# squawkbox_m_rj11_0_1_0.net
KiCad netlist of a schematic drawn in EAGLE
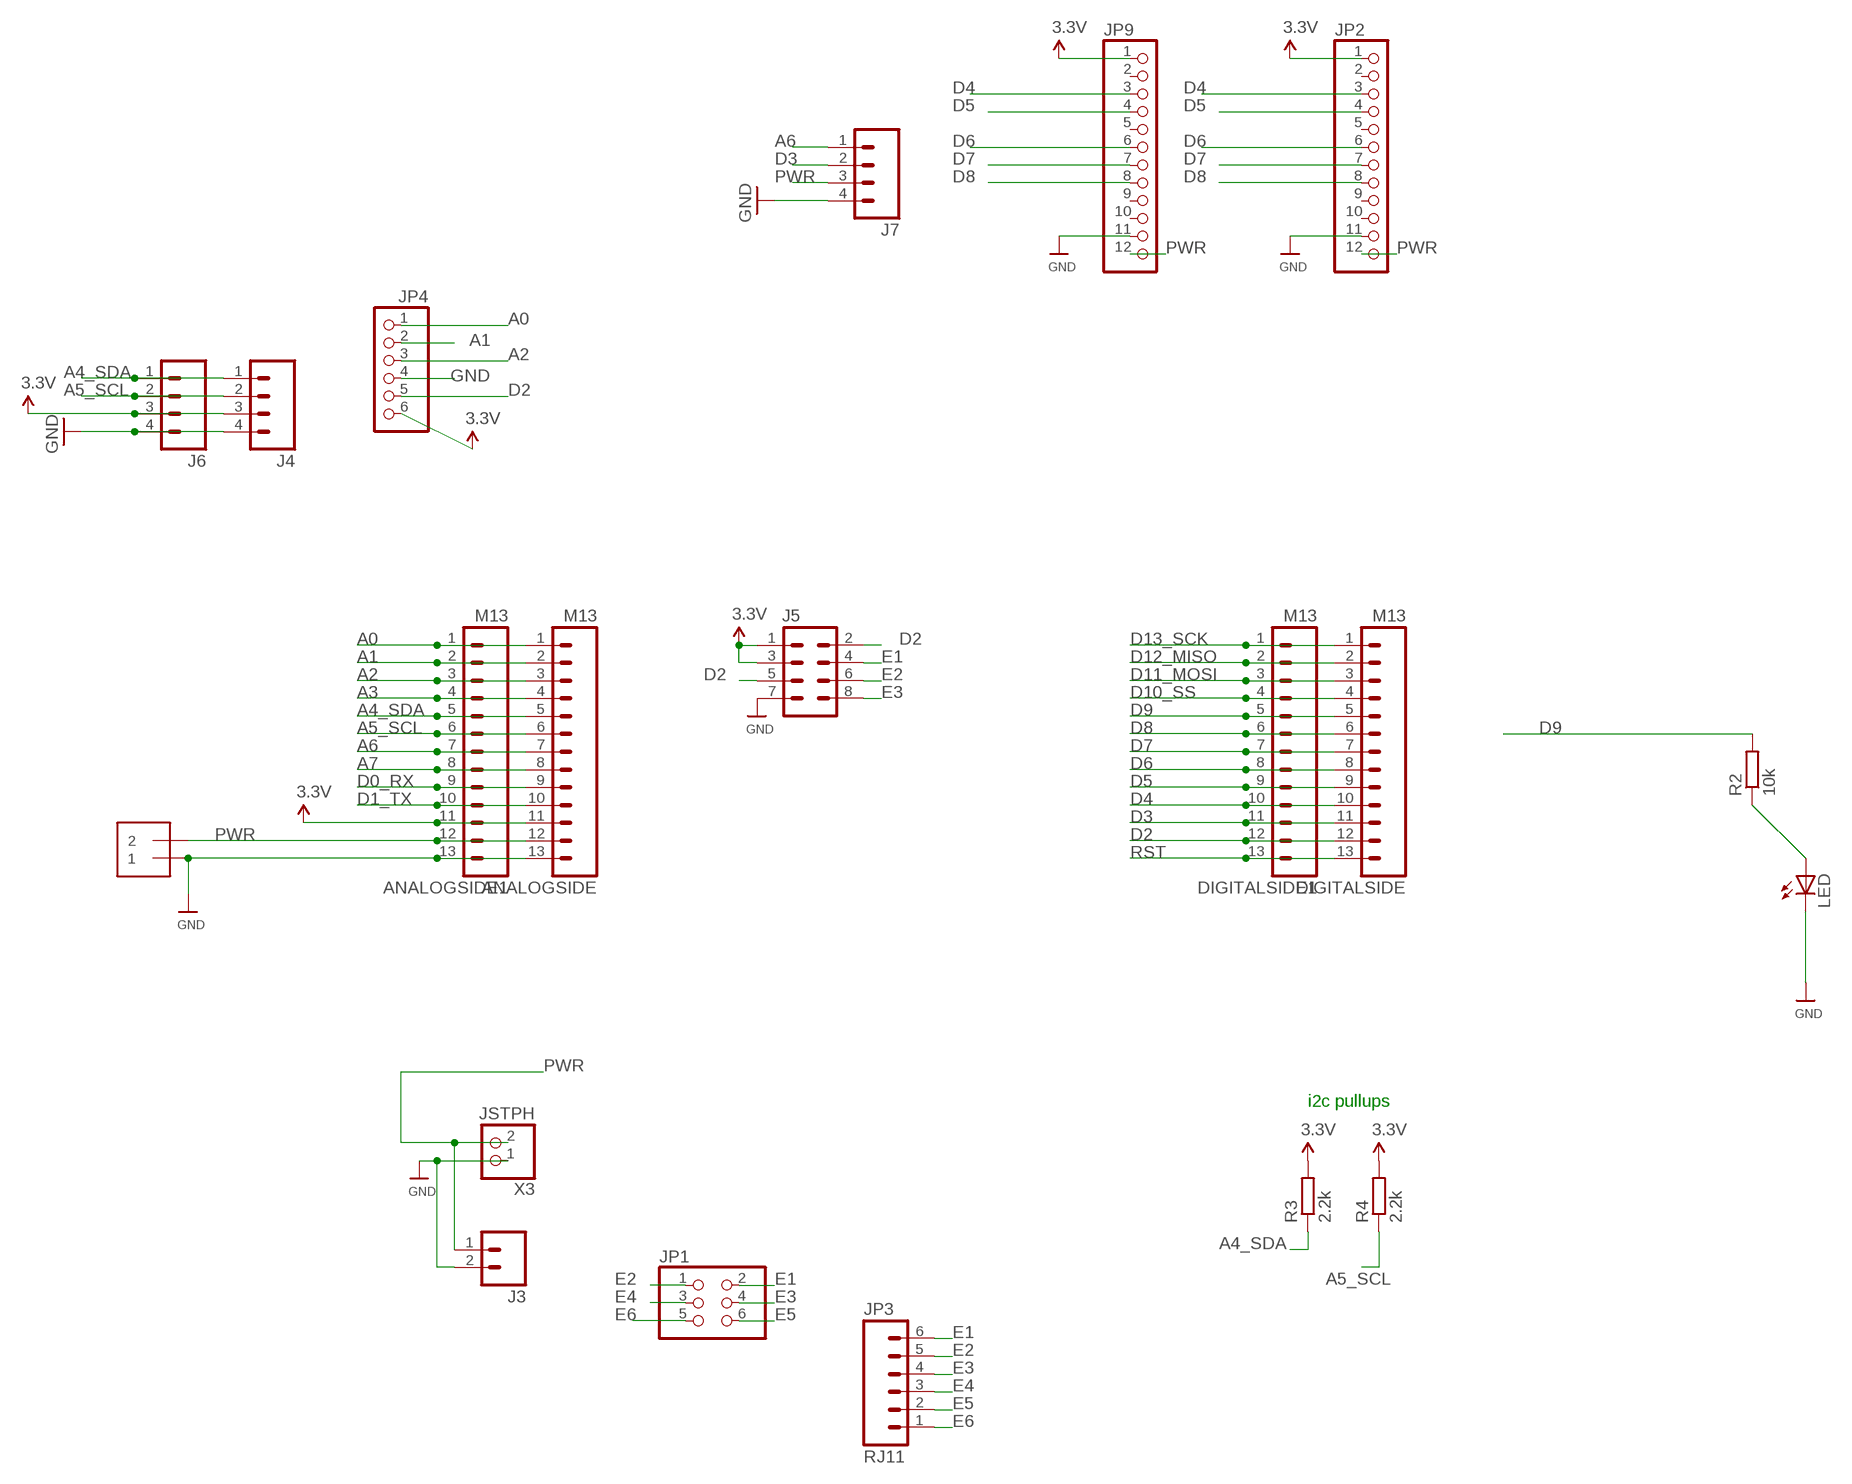
[diagram p0: schematic, sheet 1]

(export (version "E")
  (design (tool "Eeschema 10.0.6"))
  (components
    (comp (ref "ANALOGSIDE")
      (value "M13")
      (footprint "eagle-import:1X13")
      (libsource (lib "eagle-import") (part "M13"))
    )
    (comp (ref "ANALOGSIDE1")
      (value "M13")
      (footprint "eagle-import:1X13")
      (libsource (lib "eagle-import") (part "M13"))
    )
    (comp (ref "DIGITALSIDE")
      (value "M13")
      (footprint "eagle-import:1X13")
      (libsource (lib "eagle-import") (part "M13"))
    )
    (comp (ref "DIGITALSIDE1")
      (value "M13")
      (footprint "eagle-import:1X13")
      (libsource (lib "eagle-import") (part "M13"))
    )
    (comp (ref "J2")
      (value "1X2-3.5MM")
      (footprint "eagle-import:1X2-3.5MM")
      (libsource (lib "eagle-import") (part "1X2-3.5MM"))
    )
    (comp (ref "J3")
      (value "M02PTH")
      (footprint "eagle-import:1X02")
      (libsource (lib "eagle-import") (part "M02PTH"))
    )
    (comp (ref "J4")
      (value "M04PTH")
      (footprint "eagle-import:1X04")
      (libsource (lib "eagle-import") (part "M04PTH"))
    )
    (comp (ref "J5")
      (value "M04X2")
      (footprint "eagle-import:2X4")
      (libsource (lib "eagle-import") (part "M04X2"))
    )
    (comp (ref "J6")
      (value "M04SCREW")
      (footprint "eagle-import:SCREWTERMINAL-3.5MM-4")
      (libsource (lib "eagle-import") (part "M04SCREW"))
    )
    (comp (ref "J7")
      (value "M04SCREW")
      (footprint "eagle-import:SCREWTERMINAL-3.5MM-4")
      (libsource (lib "eagle-import") (part "M04SCREW"))
    )
    (comp (ref "JP1")
      (value "PINHD-2X3")
      (footprint "eagle-import:2X03")
      (libsource (lib "eagle-import") (part "PINHD-2X3"))
    )
    (comp (ref "JP2")
      (value "PINHD-1X12-CB")
      (footprint "eagle-import:1X12-CB")
      (libsource (lib "eagle-import") (part "PINHD-1X12-CB"))
    )
    (comp (ref "JP3")
      (value "RJ11")
      (footprint "eagle-import:RJ11-6")
      (libsource (lib "eagle-import") (part "RJ11-6PTH"))
    )
    (comp (ref "JP4")
      (value "PINHD-1X6-3.5MM")
      (footprint "eagle-import:1X06-3.5MM")
      (libsource (lib "eagle-import") (part "PINHD-1X6-3.5MM"))
    )
    (comp (ref "JP9")
      (value "PINHD-1X12-CB")
      (footprint "eagle-import:1X12-CB")
      (libsource (lib "eagle-import") (part "PINHD-1X12-CB"))
    )
    (comp (ref "LED")
      (value "LED3MM")
      (footprint "eagle-import:LED3MM")
      (libsource (lib "eagle-import") (part "LED3MM"))
    )
    (comp (ref "R2")
      (value "10k")
      (footprint "eagle-import:0204_7")
      (libsource (lib "eagle-import") (part "R-EU_0204/7"))
    )
    (comp (ref "R3")
      (value "2.2k")
      (footprint "eagle-import:0204_7")
      (libsource (lib "eagle-import") (part "R-EU_0204/7"))
    )
    (comp (ref "R4")
      (value "2.2k")
      (footprint "eagle-import:0204_7")
      (libsource (lib "eagle-import") (part "R-EU_0204/7"))
    )
    (comp (ref "X3")
      (value "JSTPH")
      (footprint "eagle-import:JSTPH2")
      (libsource (lib "eagle-import") (part "CON_JST_PH_2PIN"))
    )
  )
  (nets
    (net (code "1") (name "/A0") (class "Default")
      (node (ref "ANALOGSIDE") (pin "1") (pinfunction "1_1") (pintype "passive"))
      (node (ref "ANALOGSIDE1") (pin "1") (pinfunction "1_1") (pintype "passive"))
      (node (ref "JP4") (pin "1") (pinfunction "1_1") (pintype "passive"))
    )
    (net (code "2") (name "/A1") (class "Default")
      (node (ref "ANALOGSIDE") (pin "2") (pinfunction "2_2") (pintype "passive"))
      (node (ref "ANALOGSIDE1") (pin "2") (pinfunction "2_2") (pintype "passive"))
      (node (ref "JP4") (pin "2") (pinfunction "2_2") (pintype "passive"))
    )
    (net (code "3") (name "/A2") (class "Default")
      (node (ref "ANALOGSIDE") (pin "3") (pinfunction "3_3") (pintype "passive"))
      (node (ref "ANALOGSIDE1") (pin "3") (pinfunction "3_3") (pintype "passive"))
      (node (ref "JP4") (pin "3") (pinfunction "3_3") (pintype "passive"))
    )
    (net (code "4") (name "/A3") (class "Default")
      (node (ref "ANALOGSIDE") (pin "4") (pinfunction "4_4") (pintype "passive"))
      (node (ref "ANALOGSIDE1") (pin "4") (pinfunction "4_4") (pintype "passive"))
    )
    (net (code "5") (name "/A4_SDA") (class "Default")
      (node (ref "ANALOGSIDE") (pin "5") (pinfunction "5_5") (pintype "passive"))
      (node (ref "ANALOGSIDE1") (pin "5") (pinfunction "5_5") (pintype "passive"))
      (node (ref "J4") (pin "1") (pinfunction "1_1") (pintype "passive"))
      (node (ref "J6") (pin "1") (pinfunction "1_1") (pintype "passive"))
      (node (ref "R3") (pin "1") (pinfunction "1_1") (pintype "passive"))
    )
    (net (code "6") (name "/A5_SCL") (class "Default")
      (node (ref "ANALOGSIDE") (pin "6") (pinfunction "6_6") (pintype "passive"))
      (node (ref "ANALOGSIDE1") (pin "6") (pinfunction "6_6") (pintype "passive"))
      (node (ref "J4") (pin "2") (pinfunction "2_2") (pintype "passive"))
      (node (ref "J6") (pin "2") (pinfunction "2_2") (pintype "passive"))
      (node (ref "R4") (pin "1") (pinfunction "1_1") (pintype "passive"))
    )
    (net (code "7") (name "/A6") (class "Default")
      (node (ref "ANALOGSIDE") (pin "7") (pinfunction "7_7") (pintype "passive"))
      (node (ref "ANALOGSIDE1") (pin "7") (pinfunction "7_7") (pintype "passive"))
      (node (ref "J7") (pin "1") (pinfunction "1_1") (pintype "passive"))
    )
    (net (code "8") (name "/A7") (class "Default")
      (node (ref "ANALOGSIDE") (pin "8") (pinfunction "8_8") (pintype "passive"))
      (node (ref "ANALOGSIDE1") (pin "8") (pinfunction "8_8") (pintype "passive"))
    )
    (net (code "9") (name "/D0_RX") (class "Default")
      (node (ref "ANALOGSIDE") (pin "9") (pinfunction "9_9") (pintype "passive"))
      (node (ref "ANALOGSIDE1") (pin "9") (pinfunction "9_9") (pintype "passive"))
    )
    (net (code "10") (name "/D1_TX") (class "Default")
      (node (ref "ANALOGSIDE") (pin "10") (pinfunction "10_10") (pintype "passive"))
      (node (ref "ANALOGSIDE1") (pin "10") (pinfunction "10_10") (pintype "passive"))
    )
    (net (code "11") (name "/D2") (class "Default")
      (node (ref "DIGITALSIDE") (pin "12") (pinfunction "12_12") (pintype "passive"))
      (node (ref "DIGITALSIDE1") (pin "12") (pinfunction "12_12") (pintype "passive"))
      (node (ref "J5") (pin "2") (pinfunction "2_2") (pintype "passive"))
      (node (ref "J5") (pin "5") (pinfunction "5_5") (pintype "passive"))
      (node (ref "JP4") (pin "5") (pinfunction "5_5") (pintype "passive"))
    )
    (net (code "12") (name "/D3") (class "Default")
      (node (ref "DIGITALSIDE") (pin "11") (pinfunction "11_11") (pintype "passive"))
      (node (ref "DIGITALSIDE1") (pin "11") (pinfunction "11_11") (pintype "passive"))
      (node (ref "J7") (pin "2") (pinfunction "2_2") (pintype "passive"))
    )
    (net (code "13") (name "/D4") (class "Default")
      (node (ref "DIGITALSIDE") (pin "10") (pinfunction "10_10") (pintype "passive"))
      (node (ref "DIGITALSIDE1") (pin "10") (pinfunction "10_10") (pintype "passive"))
      (node (ref "JP2") (pin "3") (pinfunction "3_3") (pintype "passive"))
      (node (ref "JP9") (pin "3") (pinfunction "3_3") (pintype "passive"))
    )
    (net (code "14") (name "/D5") (class "Default")
      (node (ref "DIGITALSIDE") (pin "9") (pinfunction "9_9") (pintype "passive"))
      (node (ref "DIGITALSIDE1") (pin "9") (pinfunction "9_9") (pintype "passive"))
      (node (ref "JP2") (pin "4") (pinfunction "4_4") (pintype "passive"))
      (node (ref "JP9") (pin "4") (pinfunction "4_4") (pintype "passive"))
    )
    (net (code "15") (name "/D6") (class "Default")
      (node (ref "DIGITALSIDE") (pin "8") (pinfunction "8_8") (pintype "passive"))
      (node (ref "DIGITALSIDE1") (pin "8") (pinfunction "8_8") (pintype "passive"))
      (node (ref "JP2") (pin "6") (pinfunction "6_6") (pintype "passive"))
      (node (ref "JP9") (pin "6") (pinfunction "6_6") (pintype "passive"))
    )
    (net (code "16") (name "/D7") (class "Default")
      (node (ref "DIGITALSIDE") (pin "7") (pinfunction "7_7") (pintype "passive"))
      (node (ref "DIGITALSIDE1") (pin "7") (pinfunction "7_7") (pintype "passive"))
      (node (ref "JP2") (pin "7") (pinfunction "7_7") (pintype "passive"))
      (node (ref "JP9") (pin "7") (pinfunction "7_7") (pintype "passive"))
    )
    (net (code "17") (name "/D8") (class "Default")
      (node (ref "DIGITALSIDE") (pin "6") (pinfunction "6_6") (pintype "passive"))
      (node (ref "DIGITALSIDE1") (pin "6") (pinfunction "6_6") (pintype "passive"))
      (node (ref "JP2") (pin "8") (pinfunction "8_8") (pintype "passive"))
      (node (ref "JP9") (pin "8") (pinfunction "8_8") (pintype "passive"))
    )
    (net (code "18") (name "/D9") (class "Default")
      (node (ref "DIGITALSIDE") (pin "5") (pinfunction "5_5") (pintype "passive"))
      (node (ref "DIGITALSIDE1") (pin "5") (pinfunction "5_5") (pintype "passive"))
      (node (ref "R2") (pin "2") (pinfunction "2_2") (pintype "passive"))
    )
    (net (code "19") (name "/D10_SS") (class "Default")
      (node (ref "DIGITALSIDE") (pin "4") (pinfunction "4_4") (pintype "passive"))
      (node (ref "DIGITALSIDE1") (pin "4") (pinfunction "4_4") (pintype "passive"))
    )
    (net (code "20") (name "/D11_MOSI") (class "Default")
      (node (ref "DIGITALSIDE") (pin "3") (pinfunction "3_3") (pintype "passive"))
      (node (ref "DIGITALSIDE1") (pin "3") (pinfunction "3_3") (pintype "passive"))
    )
    (net (code "21") (name "/D12_MISO") (class "Default")
      (node (ref "DIGITALSIDE") (pin "2") (pinfunction "2_2") (pintype "passive"))
      (node (ref "DIGITALSIDE1") (pin "2") (pinfunction "2_2") (pintype "passive"))
    )
    (net (code "22") (name "/D13_SCK") (class "Default")
      (node (ref "DIGITALSIDE") (pin "1") (pinfunction "1_1") (pintype "passive"))
      (node (ref "DIGITALSIDE1") (pin "1") (pinfunction "1_1") (pintype "passive"))
    )
    (net (code "23") (name "/E1") (class "Default")
      (node (ref "J5") (pin "4") (pinfunction "4_4") (pintype "passive"))
      (node (ref "JP1") (pin "2") (pinfunction "2_2") (pintype "passive"))
      (node (ref "JP3") (pin "6") (pinfunction "6_6") (pintype "passive"))
    )
    (net (code "24") (name "/E2") (class "Default")
      (node (ref "J5") (pin "6") (pinfunction "6_6") (pintype "passive"))
      (node (ref "JP1") (pin "1") (pinfunction "1_1") (pintype "passive"))
      (node (ref "JP3") (pin "5") (pinfunction "5_5") (pintype "passive"))
    )
    (net (code "25") (name "/E3") (class "Default")
      (node (ref "J5") (pin "8") (pinfunction "8_8") (pintype "passive"))
      (node (ref "JP1") (pin "4") (pinfunction "4_4") (pintype "passive"))
      (node (ref "JP3") (pin "4") (pinfunction "4_4") (pintype "passive"))
    )
    (net (code "26") (name "/E4") (class "Default")
      (node (ref "JP1") (pin "3") (pinfunction "3_3") (pintype "passive"))
      (node (ref "JP3") (pin "3") (pinfunction "3_3") (pintype "passive"))
    )
    (net (code "27") (name "/E5") (class "Default")
      (node (ref "JP1") (pin "6") (pinfunction "6_6") (pintype "passive"))
      (node (ref "JP3") (pin "2") (pinfunction "2_2") (pintype "passive"))
    )
    (net (code "28") (name "/E6") (class "Default")
      (node (ref "JP1") (pin "5") (pinfunction "5_5") (pintype "passive"))
      (node (ref "JP3") (pin "1") (pinfunction "1_1") (pintype "passive"))
    )
    (net (code "29") (name "/PWR") (class "Default")
      (node (ref "ANALOGSIDE") (pin "12") (pinfunction "12_12") (pintype "passive"))
      (node (ref "ANALOGSIDE1") (pin "12") (pinfunction "12_12") (pintype "passive"))
      (node (ref "J2") (pin "2") (pinfunction "2_2") (pintype "passive"))
      (node (ref "J3") (pin "1") (pinfunction "1_1") (pintype "passive"))
      (node (ref "J7") (pin "3") (pinfunction "3_3") (pintype "passive"))
      (node (ref "JP2") (pin "12") (pinfunction "12_12") (pintype "passive"))
      (node (ref "JP9") (pin "12") (pinfunction "12_12") (pintype "passive"))
      (node (ref "X3") (pin "2") (pinfunction "2_2") (pintype "passive"))
    )
    (net (code "30") (name "/RST") (class "Default")
      (node (ref "DIGITALSIDE") (pin "13") (pinfunction "13_13") (pintype "passive"))
      (node (ref "DIGITALSIDE1") (pin "13") (pinfunction "13_13") (pintype "passive"))
    )
    (net (code "31") (name "3.3V") (class "Default")
      (node (ref "ANALOGSIDE") (pin "11") (pinfunction "11_11") (pintype "passive"))
      (node (ref "ANALOGSIDE1") (pin "11") (pinfunction "11_11") (pintype "passive"))
      (node (ref "J4") (pin "3") (pinfunction "3_3") (pintype "passive"))
      (node (ref "J5") (pin "1") (pinfunction "1_1") (pintype "passive"))
      (node (ref "J5") (pin "3") (pinfunction "3_3") (pintype "passive"))
      (node (ref "J6") (pin "3") (pinfunction "3_3") (pintype "passive"))
      (node (ref "JP2") (pin "1") (pinfunction "1_1") (pintype "passive"))
      (node (ref "JP4") (pin "6") (pinfunction "6_6") (pintype "passive"))
      (node (ref "JP9") (pin "1") (pinfunction "1_1") (pintype "passive"))
      (node (ref "R3") (pin "2") (pinfunction "2_2") (pintype "passive"))
      (node (ref "R4") (pin "2") (pinfunction "2_2") (pintype "passive"))
    )
    (net (code "32") (name "GND") (class "Default")
      (node (ref "ANALOGSIDE") (pin "13") (pinfunction "13_13") (pintype "passive"))
      (node (ref "ANALOGSIDE1") (pin "13") (pinfunction "13_13") (pintype "passive"))
      (node (ref "J2") (pin "1") (pinfunction "1_1") (pintype "passive"))
      (node (ref "J3") (pin "2") (pinfunction "2_2") (pintype "passive"))
      (node (ref "J4") (pin "4") (pinfunction "4_4") (pintype "passive"))
      (node (ref "J5") (pin "7") (pinfunction "7_7") (pintype "passive"))
      (node (ref "J6") (pin "4") (pinfunction "4_4") (pintype "passive"))
      (node (ref "J7") (pin "4") (pinfunction "4_4") (pintype "passive"))
      (node (ref "JP2") (pin "11") (pinfunction "11_11") (pintype "passive"))
      (node (ref "JP4") (pin "4") (pinfunction "4_4") (pintype "passive"))
      (node (ref "JP9") (pin "11") (pinfunction "11_11") (pintype "passive"))
      (node (ref "LED") (pin "K") (pinfunction "C_K") (pintype "passive"))
      (node (ref "X3") (pin "1") (pinfunction "1_1") (pintype "passive"))
    )
    (net (code "33") (name "Net-(LED-PadA)") (class "Default")
      (node (ref "LED") (pin "A") (pinfunction "A_A") (pintype "passive"))
      (node (ref "R2") (pin "1") (pinfunction "1_1") (pintype "passive"))
    )
    (net (code "34") (name "unconnected-(JP2-Pad2)") (class "Default")
      (node (ref "JP2") (pin "2") (pinfunction "2_2") (pintype "passive"))
    )
    (net (code "35") (name "unconnected-(JP2-Pad5)") (class "Default")
      (node (ref "JP2") (pin "5") (pinfunction "5_5") (pintype "passive"))
    )
    (net (code "36") (name "unconnected-(JP2-Pad9)") (class "Default")
      (node (ref "JP2") (pin "9") (pinfunction "9_9") (pintype "passive"))
    )
    (net (code "37") (name "unconnected-(JP2-Pad10)") (class "Default")
      (node (ref "JP2") (pin "10") (pinfunction "10_10") (pintype "passive"))
    )
    (net (code "38") (name "unconnected-(JP9-Pad2)") (class "Default")
      (node (ref "JP9") (pin "2") (pinfunction "2_2") (pintype "passive"))
    )
    (net (code "39") (name "unconnected-(JP9-Pad5)") (class "Default")
      (node (ref "JP9") (pin "5") (pinfunction "5_5") (pintype "passive"))
    )
    (net (code "40") (name "unconnected-(JP9-Pad9)") (class "Default")
      (node (ref "JP9") (pin "9") (pinfunction "9_9") (pintype "passive"))
    )
    (net (code "41") (name "unconnected-(JP9-Pad10)") (class "Default")
      (node (ref "JP9") (pin "10") (pinfunction "10_10") (pintype "passive"))
    )
  )
)
